# Power_Regulators.net
KiCad netlist of a schematic drawn in Altium Designer
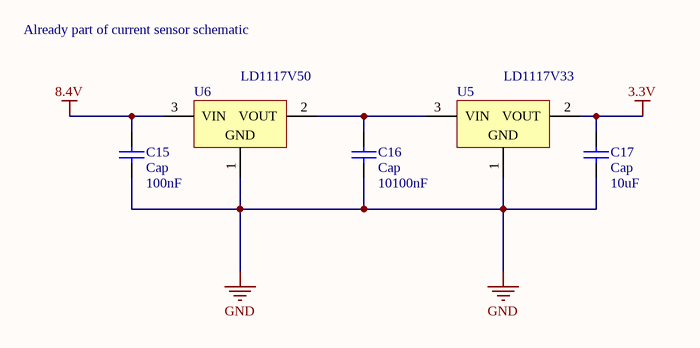
[diagram p0: Power_Regulators.SchDoc]

(export (version "E")
  (design (tool "Eeschema 10.0.6"))
  (components
    (comp (ref "C15")
      (value "Cap")
      (footprint "RAD-0.3")
      (description "Capacitor")
      (fields (field (name "ALTIUM_VALUE") "100nF") (field (name "PUBLISHER") "Altium Limited"))
      (libsource (lib "Miscellaneous Devices") (part "Cap"))
    )
    (comp (ref "C16")
      (value "Cap")
      (footprint "RAD-0.3")
      (description "Capacitor")
      (fields (field (name "ALTIUM_VALUE") "10100nF") (field (name "PUBLISHER") "Altium Limited"))
      (libsource (lib "Miscellaneous Devices") (part "Cap"))
    )
    (comp (ref "C17")
      (value "Cap")
      (footprint "RAD-0.3")
      (description "Capacitor")
      (fields (field (name "ALTIUM_VALUE") "10uF") (field (name "PUBLISHER") "Altium Limited"))
      (libsource (lib "Miscellaneous Devices") (part "Cap"))
    )
    (comp (ref "U5")
      (value "LD1117V33")
      (footprint "TO220")
      (description "Fixed Low Drop Positive Voltage Regulator, 3.3V, 3-Pin TO-220")
      (libsource (lib "Altium Content Vault") (part "PM-REG-LD1117V-SIL3"))
    )
    (comp (ref "U6")
      (value "LD1117V50")
      (footprint "TO220")
      (description "Fixed Low Drop Positive Voltage Regulator, 5V, 3-Pin TO-220")
      (libsource (lib "Altium Content Vault") (part "PM-REG-LD1117V-SIL3"))
    )
  )
  (nets
    (net (code "1") (name "3.3V") (class "Default")
      (node (ref "C17") (pin "2") (pinfunction "2_2") (pintype "passive"))
      (node (ref "U5") (pin "2") (pinfunction "VOUT_2") (pintype "power_in"))
    )
    (net (code "2") (name "8.4V") (class "Default")
      (node (ref "C15") (pin "2") (pinfunction "2_2") (pintype "passive"))
      (node (ref "U6") (pin "3") (pinfunction "VIN_3") (pintype "power_in"))
    )
    (net (code "3") (name "GND") (class "Default")
      (node (ref "C15") (pin "1") (pinfunction "1_1") (pintype "passive"))
      (node (ref "C16") (pin "1") (pinfunction "1_1") (pintype "passive"))
      (node (ref "C17") (pin "1") (pinfunction "1_1") (pintype "passive"))
      (node (ref "U5") (pin "1") (pinfunction "GND_1") (pintype "power_in"))
      (node (ref "U6") (pin "1") (pinfunction "GND_1") (pintype "power_in"))
    )
    (net (code "4") (name "Net-(U5-VIN)") (class "Default")
      (node (ref "C16") (pin "2") (pinfunction "2_2") (pintype "passive"))
      (node (ref "U5") (pin "3") (pinfunction "VIN_3") (pintype "power_in"))
      (node (ref "U6") (pin "2") (pinfunction "VOUT_2") (pintype "power_in"))
    )
  )
)
